# MCU.net
KiCad netlist of a schematic drawn in Altium Designer
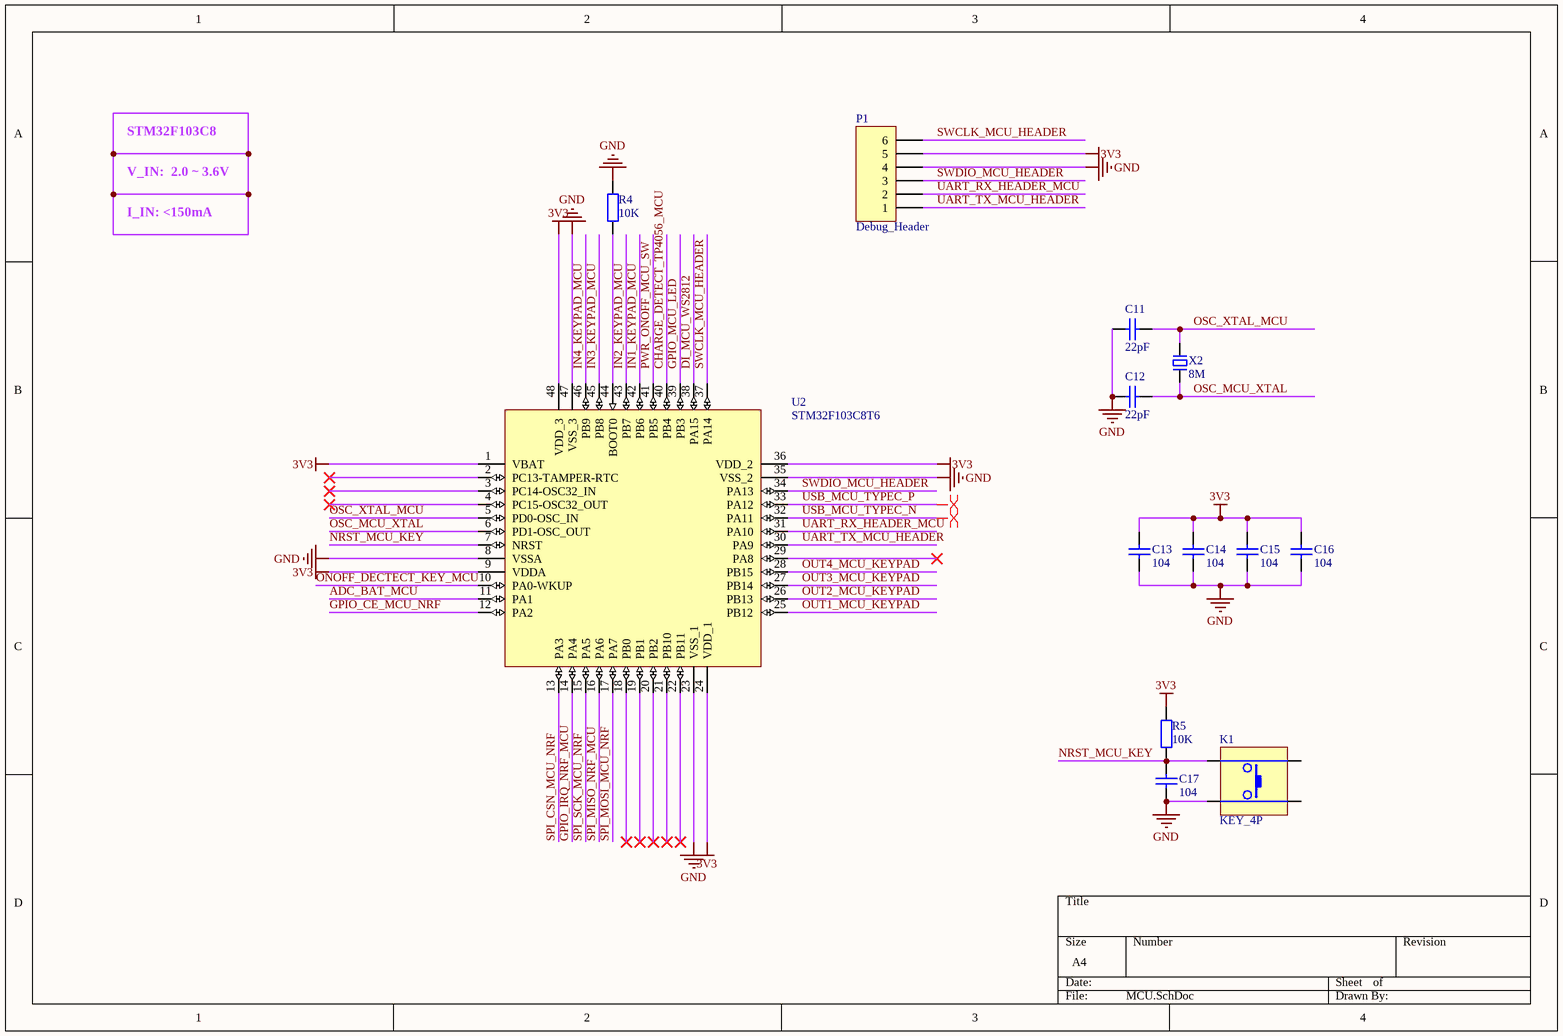
[diagram p0: MCU.SchDoc]

(export (version "E")
  (design (tool "Eeschema 10.0.6"))
  (components
    (comp (ref "C11")
      (value "22pF")
      (footprint "Cap-0603")
      (description "贴片陶瓷电容")
      (libsource (lib "Miscellaneous Base") (part "CAP"))
    )
    (comp (ref "C12")
      (value "22pF")
      (footprint "Cap-0603")
      (description "贴片陶瓷电容")
      (libsource (lib "Miscellaneous Base") (part "CAP"))
    )
    (comp (ref "C13")
      (value "104")
      (footprint "Cap-0603")
      (description "贴片陶瓷电容")
      (libsource (lib "Miscellaneous Base") (part "CAP"))
    )
    (comp (ref "C14")
      (value "104")
      (footprint "Cap-0603")
      (description "贴片陶瓷电容")
      (libsource (lib "Miscellaneous Base") (part "CAP"))
    )
    (comp (ref "C15")
      (value "104")
      (footprint "Cap-0603")
      (description "贴片陶瓷电容")
      (libsource (lib "Miscellaneous Base") (part "CAP"))
    )
    (comp (ref "C16")
      (value "104")
      (footprint "Cap-0603")
      (description "贴片陶瓷电容")
      (libsource (lib "Miscellaneous Base") (part "CAP"))
    )
    (comp (ref "C17")
      (value "104")
      (footprint "Cap-0603")
      (description "贴片陶瓷电容")
      (libsource (lib "Miscellaneous Base") (part "CAP"))
    )
    (comp (ref "K1")
      (value "KEY_4P")
      (footprint "SW-SMD-3X4X2.5")
      (libsource (lib "Miscellaneous Switch") (part "KEY_4P"))
    )
    (comp (ref "P1")
      (value "Debug_Header")
      (footprint "Header 2.54X6")
      (libsource (lib "Miscellaneous Header") (part "Header_6"))
    )
    (comp (ref "R4")
      (value "10K")
      (footprint "Res-0603")
      (description "贴片电阻")
      (libsource (lib "Miscellaneous Base") (part "RES"))
    )
    (comp (ref "R5")
      (value "10K")
      (footprint "Res-0603")
      (description "贴片电阻")
      (libsource (lib "Miscellaneous Base") (part "RES"))
    )
    (comp (ref "U2")
      (value "STM32F103C8T6")
      (footprint "STM32F103C8T6")
      (libsource (lib "Miscellaneous MCU") (part "STM32F103C8T6"))
    )
    (comp (ref "X2")
      (value "8M")
      (footprint "OSC 5032-2P")
      (description "2脚无源脚晶振")
      (libsource (lib "Miscellaneous XTAL") (part "XTAL-2P"))
    )
  )
  (nets
    (net (code "1") (name "/ADC_BAT_MCU") (class "Default")
      (node (ref "U2") (pin "11") (pinfunction "PA1_11") (pintype "bidirectional"))
    )
    (net (code "2") (name "/CHARGE_DETECT_TP4056_MCU") (class "Default")
      (node (ref "U2") (pin "40") (pinfunction "PB4_40") (pintype "bidirectional"))
    )
    (net (code "3") (name "/DI_MCU_WS2812") (class "Default")
      (node (ref "U2") (pin "38") (pinfunction "PA15_38") (pintype "bidirectional"))
    )
    (net (code "4") (name "/GPIO_CE_MCU_NRF") (class "Default")
      (node (ref "U2") (pin "12") (pinfunction "PA2_12") (pintype "bidirectional"))
    )
    (net (code "5") (name "/GPIO_IRQ_NRF_MCU") (class "Default")
      (node (ref "U2") (pin "14") (pinfunction "PA4_14") (pintype "bidirectional"))
    )
    (net (code "6") (name "/GPIO_MCU_LED") (class "Default")
      (node (ref "U2") (pin "39") (pinfunction "PB3_39") (pintype "bidirectional"))
    )
    (net (code "7") (name "/IN1_KEYPAD_MCU") (class "Default")
      (node (ref "U2") (pin "42") (pinfunction "PB6_42") (pintype "bidirectional"))
    )
    (net (code "8") (name "/IN2_KEYPAD_MCU") (class "Default")
      (node (ref "U2") (pin "43") (pinfunction "PB7_43") (pintype "bidirectional"))
    )
    (net (code "9") (name "/IN3_KEYPAD_MCU") (class "Default")
      (node (ref "U2") (pin "45") (pinfunction "PB8_45") (pintype "bidirectional"))
    )
    (net (code "10") (name "/IN4_KEYPAD_MCU") (class "Default")
      (node (ref "U2") (pin "46") (pinfunction "PB9_46") (pintype "bidirectional"))
    )
    (net (code "11") (name "/NRST_MCU_KEY") (class "Default")
      (node (ref "C17") (pin "2") (pinfunction "2_2") (pintype "passive"))
      (node (ref "K1") (pin "3") (pinfunction "3_3") (pintype "passive"))
      (node (ref "R5") (pin "1") (pinfunction "1_1") (pintype "passive"))
      (node (ref "U2") (pin "7") (pinfunction "NRST_7") (pintype "bidirectional"))
    )
    (net (code "12") (name "/ONOFF_DECTECT_KEY_MCU") (class "Default")
      (node (ref "U2") (pin "10") (pinfunction "PA0-WKUP_10") (pintype "bidirectional"))
    )
    (net (code "13") (name "/OSC_MCU_XTAL") (class "Default")
      (node (ref "C12") (pin "2") (pinfunction "2_2") (pintype "passive"))
      (node (ref "U2") (pin "6") (pinfunction "PD1-OSC_OUT_6") (pintype "bidirectional"))
      (node (ref "X2") (pin "1") (pinfunction "1_1") (pintype "passive"))
    )
    (net (code "14") (name "/OSC_XTAL_MCU") (class "Default")
      (node (ref "C11") (pin "2") (pinfunction "2_2") (pintype "passive"))
      (node (ref "U2") (pin "5") (pinfunction "PD0-OSC_IN_5") (pintype "bidirectional"))
      (node (ref "X2") (pin "2") (pinfunction "2_2") (pintype "passive"))
    )
    (net (code "15") (name "/OUT1_MCU_KEYPAD") (class "Default")
      (node (ref "U2") (pin "25") (pinfunction "PB12_25") (pintype "bidirectional"))
    )
    (net (code "16") (name "/OUT2_MCU_KEYPAD") (class "Default")
      (node (ref "U2") (pin "26") (pinfunction "PB13_26") (pintype "bidirectional"))
    )
    (net (code "17") (name "/OUT3_MCU_KEYPAD") (class "Default")
      (node (ref "U2") (pin "27") (pinfunction "PB14_27") (pintype "bidirectional"))
    )
    (net (code "18") (name "/OUT4_MCU_KEYPAD") (class "Default")
      (node (ref "U2") (pin "28") (pinfunction "PB15_28") (pintype "bidirectional"))
    )
    (net (code "19") (name "/PWR_ONOFF_MCU_SW") (class "Default")
      (node (ref "U2") (pin "41") (pinfunction "PB5_41") (pintype "bidirectional"))
    )
    (net (code "20") (name "/SPI_CSN_MCU_NRF") (class "Default")
      (node (ref "U2") (pin "13") (pinfunction "PA3_13") (pintype "bidirectional"))
    )
    (net (code "21") (name "/SPI_MISO_NRF_MCU") (class "Default")
      (node (ref "U2") (pin "16") (pinfunction "PA6_16") (pintype "bidirectional"))
    )
    (net (code "22") (name "/SPI_MOSI_MCU_NRF") (class "Default")
      (node (ref "U2") (pin "17") (pinfunction "PA7_17") (pintype "bidirectional"))
    )
    (net (code "23") (name "/SPI_SCK_MCU_NRF") (class "Default")
      (node (ref "U2") (pin "15") (pinfunction "PA5_15") (pintype "bidirectional"))
    )
    (net (code "24") (name "/SWCLK_MCU_HEADER") (class "Default")
      (node (ref "P1") (pin "6") (pinfunction "6_6") (pintype "passive"))
      (node (ref "U2") (pin "37") (pinfunction "PA14_37") (pintype "bidirectional"))
    )
    (net (code "25") (name "/SWDIO_MCU_HEADER") (class "Default")
      (node (ref "P1") (pin "3") (pinfunction "3_3") (pintype "passive"))
      (node (ref "U2") (pin "34") (pinfunction "PA13_34") (pintype "bidirectional"))
    )
    (net (code "26") (name "/UART_RX_HEADER_MCU") (class "Default")
      (node (ref "P1") (pin "2") (pinfunction "2_2") (pintype "passive"))
      (node (ref "U2") (pin "31") (pinfunction "PA10_31") (pintype "bidirectional"))
    )
    (net (code "27") (name "/UART_TX_MCU_HEADER") (class "Default")
      (node (ref "P1") (pin "1") (pinfunction "1_1") (pintype "passive"))
      (node (ref "U2") (pin "30") (pinfunction "PA9_30") (pintype "bidirectional"))
    )
    (net (code "28") (name "/USB_MCU_TYPEC_N") (class "Default")
      (node (ref "U2") (pin "32") (pinfunction "PA11_32") (pintype "bidirectional"))
    )
    (net (code "29") (name "/USB_MCU_TYPEC_P") (class "Default")
      (node (ref "U2") (pin "33") (pinfunction "PA12_33") (pintype "bidirectional"))
    )
    (net (code "30") (name "3V3") (class "Default")
      (node (ref "C13") (pin "2") (pinfunction "2_2") (pintype "passive"))
      (node (ref "C14") (pin "2") (pinfunction "2_2") (pintype "passive"))
      (node (ref "C15") (pin "2") (pinfunction "2_2") (pintype "passive"))
      (node (ref "C16") (pin "2") (pinfunction "2_2") (pintype "passive"))
      (node (ref "P1") (pin "5") (pinfunction "5_5") (pintype "passive"))
      (node (ref "R5") (pin "2") (pinfunction "2_2") (pintype "passive"))
      (node (ref "U2") (pin "1") (pinfunction "VBAT_1") (pintype "power_in"))
      (node (ref "U2") (pin "24") (pinfunction "VDD_1_24") (pintype "power_in"))
      (node (ref "U2") (pin "36") (pinfunction "VDD_2_36") (pintype "power_in"))
      (node (ref "U2") (pin "48") (pinfunction "VDD_3_48") (pintype "power_in"))
      (node (ref "U2") (pin "9") (pinfunction "VDDA_9") (pintype "power_in"))
    )
    (net (code "31") (name "GND") (class "Default")
      (node (ref "C11") (pin "1") (pinfunction "1_1") (pintype "passive"))
      (node (ref "C12") (pin "1") (pinfunction "1_1") (pintype "passive"))
      (node (ref "C13") (pin "1") (pinfunction "1_1") (pintype "passive"))
      (node (ref "C14") (pin "1") (pinfunction "1_1") (pintype "passive"))
      (node (ref "C15") (pin "1") (pinfunction "1_1") (pintype "passive"))
      (node (ref "C16") (pin "1") (pinfunction "1_1") (pintype "passive"))
      (node (ref "C17") (pin "1") (pinfunction "1_1") (pintype "passive"))
      (node (ref "K1") (pin "4") (pinfunction "4_4") (pintype "passive"))
      (node (ref "P1") (pin "4") (pinfunction "4_4") (pintype "passive"))
      (node (ref "R4") (pin "2") (pinfunction "2_2") (pintype "passive"))
      (node (ref "U2") (pin "23") (pinfunction "VSS_1_23") (pintype "power_in"))
      (node (ref "U2") (pin "35") (pinfunction "VSS_2_35") (pintype "power_in"))
      (node (ref "U2") (pin "47") (pinfunction "VSS_3_47") (pintype "power_in"))
      (node (ref "U2") (pin "8") (pinfunction "VSSA_8") (pintype "power_in"))
    )
    (net (code "32") (name "Net-(U2-BOOT0)") (class "Default")
      (node (ref "R4") (pin "1") (pinfunction "1_1") (pintype "passive"))
      (node (ref "U2") (pin "44") (pinfunction "BOOT0_44") (pintype "input"))
    )
    (net (code "33") (name "unconnected-(K1-Pad1)") (class "Default")
      (node (ref "K1") (pin "1") (pinfunction "1_1") (pintype "passive"))
    )
    (net (code "34") (name "unconnected-(K1-Pad2)") (class "Default")
      (node (ref "K1") (pin "2") (pinfunction "2_2") (pintype "passive"))
    )
    (net (code "35") (name "unconnected-(U2-PA8-Pad29)") (class "Default")
      (node (ref "U2") (pin "29") (pinfunction "PA8_29") (pintype "bidirectional+no_connect"))
    )
    (net (code "36") (name "unconnected-(U2-PB0-Pad18)") (class "Default")
      (node (ref "U2") (pin "18") (pinfunction "PB0_18") (pintype "bidirectional+no_connect"))
    )
    (net (code "37") (name "unconnected-(U2-PB1-Pad19)") (class "Default")
      (node (ref "U2") (pin "19") (pinfunction "PB1_19") (pintype "bidirectional+no_connect"))
    )
    (net (code "38") (name "unconnected-(U2-PB2-Pad20)") (class "Default")
      (node (ref "U2") (pin "20") (pinfunction "PB2_20") (pintype "bidirectional+no_connect"))
    )
    (net (code "39") (name "unconnected-(U2-PB10-Pad21)") (class "Default")
      (node (ref "U2") (pin "21") (pinfunction "PB10_21") (pintype "bidirectional+no_connect"))
    )
    (net (code "40") (name "unconnected-(U2-PB11-Pad22)") (class "Default")
      (node (ref "U2") (pin "22") (pinfunction "PB11_22") (pintype "bidirectional+no_connect"))
    )
    (net (code "41") (name "unconnected-(U2-PC13-TAMPER-RTC-Pad2)") (class "Default")
      (node (ref "U2") (pin "2") (pinfunction "PC13-TAMPER-RTC_2") (pintype "bidirectional+no_connect"))
    )
    (net (code "42") (name "unconnected-(U2-PC14-OSC32_IN-Pad3)") (class "Default")
      (node (ref "U2") (pin "3") (pinfunction "PC14-OSC32_IN_3") (pintype "bidirectional+no_connect"))
    )
    (net (code "43") (name "unconnected-(U2-PC15-OSC32_OUT-Pad4)") (class "Default")
      (node (ref "U2") (pin "4") (pinfunction "PC15-OSC32_OUT_4") (pintype "bidirectional+no_connect"))
    )
  )
)
